# MAIN.net
KiCad netlist of a schematic drawn in Altium Designer
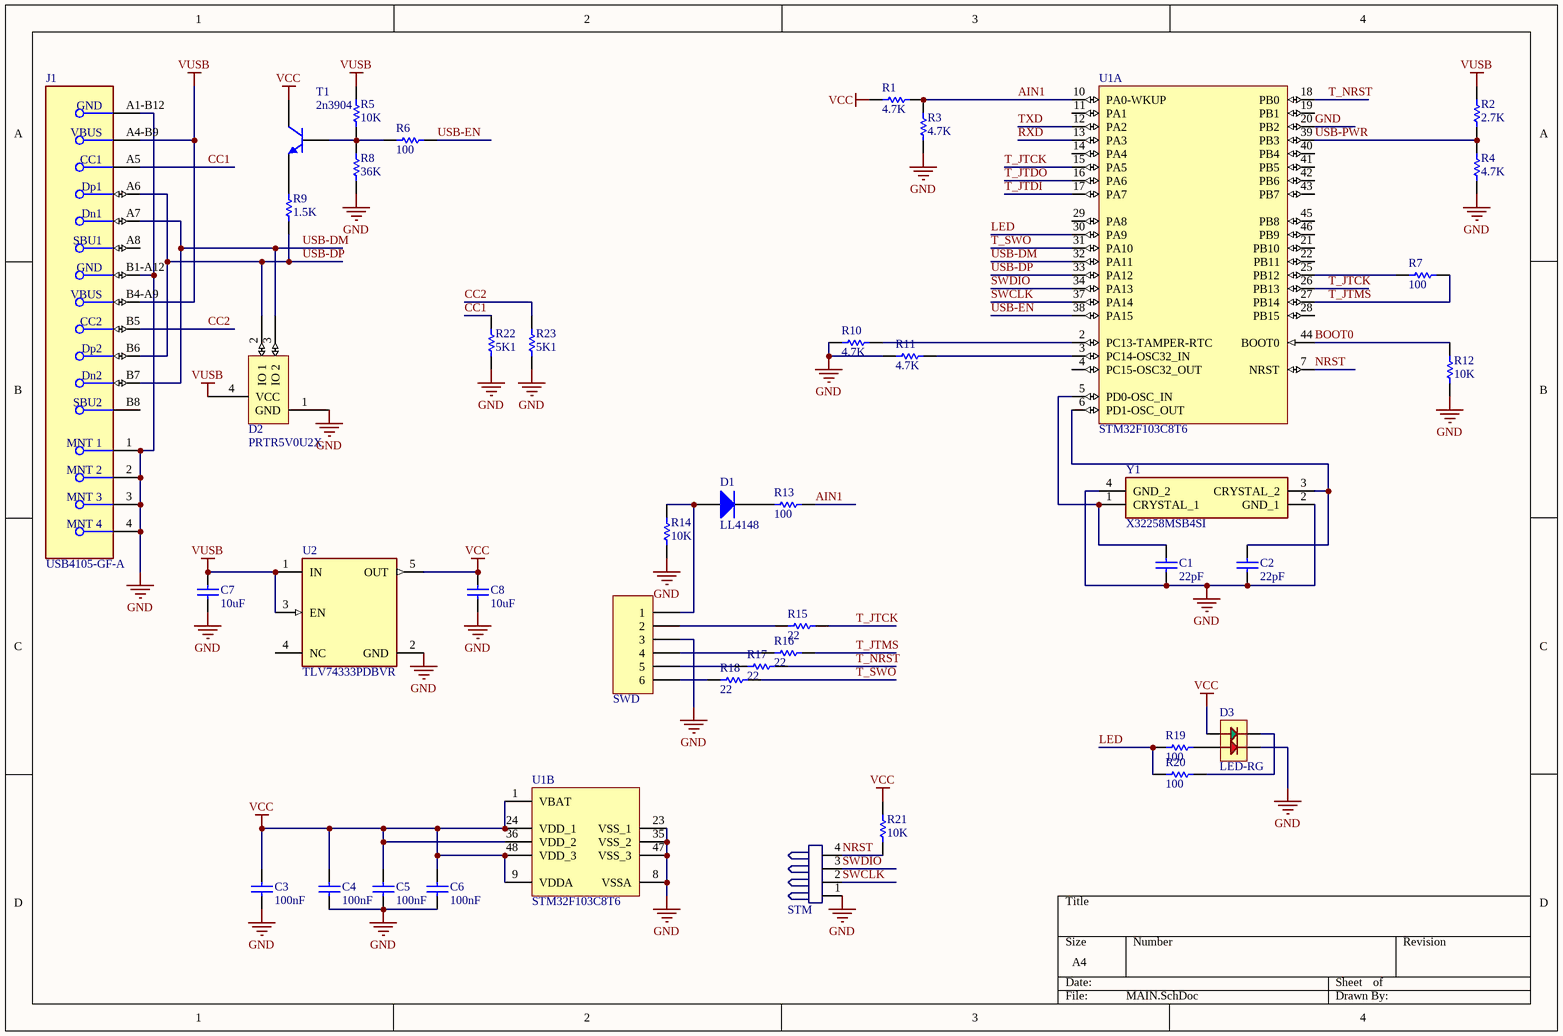
[diagram p0: MAIN.SchDoc]

(export (version "E")
  (design (tool "Eeschema 10.0.6"))
  (components
    (comp (ref "C1")
      (value "22pF")
      (footprint "C603")
      (description "Capacitor")
      (fields (field (name "DESIGNER") "Parsa Malekpour"))
      (libsource (lib "ParsaLibrary") (part "Cap"))
    )
    (comp (ref "C2")
      (value "22pF")
      (footprint "C603")
      (description "Capacitor")
      (fields (field (name "DESIGNER") "Parsa Malekpour"))
      (libsource (lib "ParsaLibrary") (part "Cap"))
    )
    (comp (ref "C3")
      (value "100nF")
      (footprint "C603")
      (description "Capacitor")
      (fields (field (name "DESIGNER") "Parsa Malekpour"))
      (libsource (lib "ParsaLibrary") (part "Cap"))
    )
    (comp (ref "C4")
      (value "100nF")
      (footprint "C603")
      (description "Capacitor")
      (fields (field (name "DESIGNER") "Parsa Malekpour"))
      (libsource (lib "ParsaLibrary") (part "Cap"))
    )
    (comp (ref "C5")
      (value "100nF")
      (footprint "C603")
      (description "Capacitor")
      (fields (field (name "DESIGNER") "Parsa Malekpour"))
      (libsource (lib "ParsaLibrary") (part "Cap"))
    )
    (comp (ref "C6")
      (value "100nF")
      (footprint "C603")
      (description "Capacitor")
      (fields (field (name "DESIGNER") "Parsa Malekpour"))
      (libsource (lib "ParsaLibrary") (part "Cap"))
    )
    (comp (ref "C7")
      (value "10uF")
      (footprint "C805")
      (description "Capacitor")
      (fields (field (name "DESIGNER") "Parsa Malekpour"))
      (libsource (lib "ParsaLibrary") (part "Cap"))
    )
    (comp (ref "C8")
      (value "10uF")
      (footprint "C805")
      (description "Capacitor")
      (fields (field (name "DESIGNER") "Parsa Malekpour"))
      (libsource (lib "ParsaLibrary") (part "Cap"))
    )
    (comp (ref "D1") (value "LL4148") (footprint "SOD-80") (libsource (lib "ParsaLibrary") (part "LL4148")))
    (comp (ref "D2")
      (value "PRTR5V0U2X")
      (footprint "SOT-143B")
      (description "Ultra low capacitance double rail-to-rail ESD protection diode")
      (libsource (lib "ParsaLibrary") (part "PRTR5V0U2X"))
    )
    (comp (ref "D3")
      (value "LED-RG")
      (footprint "LED-1210")
      (libsource (lib "ParsaLibrary") (part "LED-RG-4"))
    )
    (comp (ref "J1")
      (value "USB4105-GF-A")
      (footprint "FP-USB4105-GF-A-MFG")
      (description "CONN RCPT USB2.0 TYPEC 5A")
      (fields
        (field (name "MANUFACTURER") "GCT")
        (field (name "OCTOPART") "https://octopart.com/usb4105-gf-a-gct-106627878")
      )
      (libsource (lib "Altium Content Vault") (part "e7c17a616881a82b79941196b4bec10"))
    )
    (comp (ref "R1")
      (value "4.7K")
      (footprint "R0603")
      (description "Resistor")
      (fields (field (name "DESIGNER") "Parsa Malekpour"))
      (libsource (lib "ParsaLibrary") (part "Resistor"))
    )
    (comp (ref "R2")
      (value "2.7K")
      (footprint "R0603")
      (description "Resistor")
      (fields (field (name "DESIGNER") "Parsa Malekpour"))
      (libsource (lib "ParsaLibrary") (part "Resistor"))
    )
    (comp (ref "R3")
      (value "4.7K")
      (footprint "R0603")
      (description "Resistor")
      (fields (field (name "DESIGNER") "Parsa Malekpour"))
      (libsource (lib "ParsaLibrary") (part "Resistor"))
    )
    (comp (ref "R4")
      (value "4.7K")
      (footprint "R0603")
      (description "Resistor")
      (fields (field (name "DESIGNER") "Parsa Malekpour"))
      (libsource (lib "ParsaLibrary") (part "Resistor"))
    )
    (comp (ref "R5")
      (value "10K")
      (footprint "R0603")
      (description "Resistor")
      (fields (field (name "DESIGNER") "Parsa Malekpour"))
      (libsource (lib "ParsaLibrary") (part "Resistor"))
    )
    (comp (ref "R6")
      (value "100")
      (footprint "R0603")
      (description "Resistor")
      (fields (field (name "DESIGNER") "Parsa Malekpour"))
      (libsource (lib "ParsaLibrary") (part "Resistor"))
    )
    (comp (ref "R7")
      (value "100")
      (footprint "R0603")
      (description "Resistor")
      (fields (field (name "DESIGNER") "Parsa Malekpour"))
      (libsource (lib "ParsaLibrary") (part "Resistor"))
    )
    (comp (ref "R8")
      (value "36K")
      (footprint "R0603")
      (description "Resistor")
      (fields (field (name "DESIGNER") "Parsa Malekpour"))
      (libsource (lib "ParsaLibrary") (part "Resistor"))
    )
    (comp (ref "R9")
      (value "1.5K")
      (footprint "R0603")
      (description "Resistor")
      (fields (field (name "DESIGNER") "Parsa Malekpour"))
      (libsource (lib "ParsaLibrary") (part "Resistor"))
    )
    (comp (ref "R10")
      (value "4.7K")
      (footprint "R0603")
      (description "Resistor")
      (fields (field (name "DESIGNER") "Parsa Malekpour"))
      (libsource (lib "ParsaLibrary") (part "Resistor"))
    )
    (comp (ref "R11")
      (value "4.7K")
      (footprint "R0603")
      (description "Resistor")
      (fields (field (name "DESIGNER") "Parsa Malekpour"))
      (libsource (lib "ParsaLibrary") (part "Resistor"))
    )
    (comp (ref "R12")
      (value "10K")
      (footprint "R0603")
      (description "Resistor")
      (fields (field (name "DESIGNER") "Parsa Malekpour"))
      (libsource (lib "ParsaLibrary") (part "Resistor"))
    )
    (comp (ref "R13")
      (value "100")
      (footprint "R0603")
      (description "Resistor")
      (fields (field (name "DESIGNER") "Parsa Malekpour"))
      (libsource (lib "ParsaLibrary") (part "Resistor"))
    )
    (comp (ref "R14")
      (value "10K")
      (footprint "R0603")
      (description "Resistor")
      (fields (field (name "DESIGNER") "Parsa Malekpour"))
      (libsource (lib "ParsaLibrary") (part "Resistor"))
    )
    (comp (ref "R15")
      (value "22")
      (footprint "R0603")
      (description "Resistor")
      (fields (field (name "DESIGNER") "Parsa Malekpour"))
      (libsource (lib "ParsaLibrary") (part "Resistor"))
    )
    (comp (ref "R16")
      (value "22")
      (footprint "R0603")
      (description "Resistor")
      (fields (field (name "DESIGNER") "Parsa Malekpour"))
      (libsource (lib "ParsaLibrary") (part "Resistor"))
    )
    (comp (ref "R17")
      (value "22")
      (footprint "R0603")
      (description "Resistor")
      (fields (field (name "DESIGNER") "Parsa Malekpour"))
      (libsource (lib "ParsaLibrary") (part "Resistor"))
    )
    (comp (ref "R18")
      (value "22")
      (footprint "R0603")
      (description "Resistor")
      (fields (field (name "DESIGNER") "Parsa Malekpour"))
      (libsource (lib "ParsaLibrary") (part "Resistor"))
    )
    (comp (ref "R19")
      (value "100")
      (footprint "R0603")
      (description "Resistor")
      (fields (field (name "DESIGNER") "Parsa Malekpour"))
      (libsource (lib "ParsaLibrary") (part "Resistor"))
    )
    (comp (ref "R20")
      (value "100")
      (footprint "R0603")
      (description "Resistor")
      (fields (field (name "DESIGNER") "Parsa Malekpour"))
      (libsource (lib "ParsaLibrary") (part "Resistor"))
    )
    (comp (ref "R21")
      (value "10K")
      (footprint "R0603")
      (description "Resistor")
      (fields (field (name "DESIGNER") "Parsa Malekpour"))
      (libsource (lib "ParsaLibrary") (part "Resistor"))
    )
    (comp (ref "R22")
      (value "5K1")
      (footprint "R0603")
      (description "Resistor")
      (fields (field (name "DESIGNER") "Parsa Malekpour"))
      (libsource (lib "ParsaLibrary") (part "Resistor"))
    )
    (comp (ref "R23")
      (value "5K1")
      (footprint "R0603")
      (description "Resistor")
      (fields (field (name "DESIGNER") "Parsa Malekpour"))
      (libsource (lib "ParsaLibrary") (part "Resistor"))
    )
    (comp (ref "STM")
      (value "PHDR 4")
      (footprint "PH-4")
      (description "PinHeader")
      (libsource (lib "ParsaLibrary") (part "PHDR 4"))
    )
    (comp (ref "SWD") (value "CONN-6") (footprint "XH-6") (libsource (lib "ParsaLibrary") (part "CONN-6")))
    (comp (ref "T1") (value "2n3904") (footprint "SOT-23-3") (libsource (lib "ParsaLibrary") (part "2n3904")))
    (comp (ref "U1")
      (value "STM32F103C8T6")
      (footprint "LQFP-48")
      (libsource (lib "STMicroelectronics STM32 F1") (part "STM32F103C8T6"))
    )
    (comp (ref "U2")
      (value "TLV74333PDBVR")
      (footprint "FP-DBV0005A-MFG")
      (description "Linear Voltage Regulator IC  1 Output  300mA SOT-23-5")
      (fields (field (name "OCTOPART") "https://octopart.com/tlv74333pdbvr-texas+instruments-84791760"))
      (libsource (lib "Altium Content Vault") (part "3a8dd6e68b3b0d4ea301bae8a2f3989"))
    )
    (comp (ref "Y1")
      (value "X32258MSB4SI")
      (footprint "SamacSys:SMD3225_4P12288MHZ12PF10PPM4085")
      (description "Crystal or Oscillator")
      (fields (field (name "MANUFACTURER_PART_NUMBER") "SMD-3225_4P 12.288MHZ 12PF 10PPM -40~+85℃"))
      (libsource (lib "*") (part "SMD-3225_4P_12.288MHZ_12PF_10PPM_-40~+85"))
    )
  )
  (nets
    (net (code "1") (name "/AIN1") (class "Default")
      (node (ref "R1") (pin "1") (pinfunction "1_1") (pintype "passive"))
      (node (ref "R13") (pin "2") (pinfunction "2_2") (pintype "passive"))
      (node (ref "R3") (pin "2") (pinfunction "2_2") (pintype "passive"))
      (node (ref "U1") (pin "10") (pinfunction "PA0-WKUP_10") (pintype "bidirectional"))
    )
    (net (code "2") (name "/BOOT0") (class "Default")
      (node (ref "R12") (pin "2") (pinfunction "2_2") (pintype "passive"))
      (node (ref "U1") (pin "44") (pinfunction "BOOT0_44") (pintype "input"))
    )
    (net (code "3") (name "/CC1") (class "Default")
      (node (ref "J1") (pin "A5") (pinfunction "CC1_A5") (pintype "power_in"))
      (node (ref "R22") (pin "1") (pinfunction "1_1") (pintype "passive"))
    )
    (net (code "4") (name "/CC2") (class "Default")
      (node (ref "J1") (pin "B5") (pinfunction "CC2_B5") (pintype "bidirectional"))
      (node (ref "R23") (pin "1") (pinfunction "1_1") (pintype "passive"))
    )
    (net (code "5") (name "/LED") (class "Default")
      (node (ref "R19") (pin "2") (pinfunction "2_2") (pintype "passive"))
      (node (ref "R20") (pin "2") (pinfunction "2_2") (pintype "passive"))
      (node (ref "U1") (pin "30") (pinfunction "PA9_30") (pintype "bidirectional"))
    )
    (net (code "6") (name "/NRST") (class "Default")
      (node (ref "R21") (pin "1") (pinfunction "1_1") (pintype "passive"))
      (node (ref "STM") (pin "4") (pinfunction "4_4") (pintype "passive"))
      (node (ref "U1") (pin "7") (pinfunction "NRST_7") (pintype "bidirectional"))
    )
    (net (code "7") (name "/RXD") (class "Default")
      (node (ref "U1") (pin "13") (pinfunction "PA3_13") (pintype "bidirectional"))
    )
    (net (code "8") (name "/SWCLK") (class "Default")
      (node (ref "STM") (pin "2") (pinfunction "2_2") (pintype "passive"))
      (node (ref "U1") (pin "37") (pinfunction "PA14_37") (pintype "bidirectional"))
    )
    (net (code "9") (name "/SWDIO") (class "Default")
      (node (ref "STM") (pin "3") (pinfunction "3_3") (pintype "passive"))
      (node (ref "U1") (pin "34") (pinfunction "PA13_34") (pintype "bidirectional"))
    )
    (net (code "10") (name "/TXD") (class "Default")
      (node (ref "U1") (pin "12") (pinfunction "PA2_12") (pintype "bidirectional"))
    )
    (net (code "11") (name "/T_JTCK") (class "Default")
      (node (ref "R15") (pin "1") (pinfunction "1_1") (pintype "passive"))
      (node (ref "U1") (pin "15") (pinfunction "PA5_15") (pintype "bidirectional"))
      (node (ref "U1") (pin "26") (pinfunction "PB13_26") (pintype "bidirectional"))
    )
    (net (code "12") (name "/T_JTDI") (class "Default")
      (node (ref "U1") (pin "17") (pinfunction "PA7_17") (pintype "bidirectional"))
    )
    (net (code "13") (name "/T_JTDO") (class "Default")
      (node (ref "U1") (pin "16") (pinfunction "PA6_16") (pintype "bidirectional"))
    )
    (net (code "14") (name "/T_JTMS") (class "Default")
      (node (ref "R16") (pin "1") (pinfunction "1_1") (pintype "passive"))
      (node (ref "R7") (pin "1") (pinfunction "1_1") (pintype "passive"))
      (node (ref "U1") (pin "27") (pinfunction "PB14_27") (pintype "bidirectional"))
    )
    (net (code "15") (name "/T_NRST") (class "Default")
      (node (ref "R17") (pin "1") (pinfunction "1_1") (pintype "passive"))
      (node (ref "U1") (pin "18") (pinfunction "PB0_18") (pintype "bidirectional"))
    )
    (net (code "16") (name "/T_SWO") (class "Default")
      (node (ref "R18") (pin "1") (pinfunction "1_1") (pintype "passive"))
      (node (ref "U1") (pin "31") (pinfunction "PA10_31") (pintype "bidirectional"))
    )
    (net (code "17") (name "/USB-DM") (class "Default")
      (node (ref "D2") (pin "3") (pinfunction "IO_2_3") (pintype "bidirectional"))
      (node (ref "J1") (pin "A7") (pinfunction "Dn1_A7") (pintype "bidirectional"))
      (node (ref "J1") (pin "B7") (pinfunction "Dn2_B7") (pintype "bidirectional"))
      (node (ref "U1") (pin "32") (pinfunction "PA11_32") (pintype "bidirectional"))
    )
    (net (code "18") (name "/USB-DP") (class "Default")
      (node (ref "D2") (pin "2") (pinfunction "IO_1_2") (pintype "bidirectional"))
      (node (ref "J1") (pin "A6") (pinfunction "Dp1_A6") (pintype "bidirectional"))
      (node (ref "J1") (pin "B6") (pinfunction "Dp2_B6") (pintype "bidirectional"))
      (node (ref "R9") (pin "2") (pinfunction "2_2") (pintype "passive"))
      (node (ref "U1") (pin "33") (pinfunction "PA12_33") (pintype "bidirectional"))
    )
    (net (code "19") (name "/USB-EN") (class "Default")
      (node (ref "R6") (pin "2") (pinfunction "2_2") (pintype "passive"))
      (node (ref "U1") (pin "38") (pinfunction "PA15_38") (pintype "bidirectional"))
    )
    (net (code "20") (name "/USB-PWR") (class "Default")
      (node (ref "R2") (pin "2") (pinfunction "2_2") (pintype "passive"))
      (node (ref "R4") (pin "2") (pinfunction "2_2") (pintype "passive"))
      (node (ref "U1") (pin "39") (pinfunction "PB3_39") (pintype "bidirectional"))
    )
    (net (code "21") (name "GND") (class "Default")
      (node (ref "C1") (pin "1") (pinfunction "1_1") (pintype "passive"))
      (node (ref "C2") (pin "1") (pinfunction "1_1") (pintype "passive"))
      (node (ref "C3") (pin "1") (pinfunction "1_1") (pintype "passive"))
      (node (ref "C4") (pin "1") (pinfunction "1_1") (pintype "passive"))
      (node (ref "C5") (pin "1") (pinfunction "1_1") (pintype "passive"))
      (node (ref "C6") (pin "1") (pinfunction "1_1") (pintype "passive"))
      (node (ref "C7") (pin "1") (pinfunction "1_1") (pintype "passive"))
      (node (ref "C8") (pin "1") (pinfunction "1_1") (pintype "passive"))
      (node (ref "D2") (pin "1") (pinfunction "GND_1") (pintype "power_in"))
      (node (ref "D3") (pin "3") (pinfunction "RED-C_3") (pintype "passive"))
      (node (ref "J1") (pin "1") (pinfunction "MNT_1_1") (pintype "power_in"))
      (node (ref "J1") (pin "2") (pinfunction "MNT_2_2") (pintype "power_in"))
      (node (ref "J1") (pin "3") (pinfunction "MNT_3_3") (pintype "power_in"))
      (node (ref "J1") (pin "4") (pinfunction "MNT_4_4") (pintype "power_in"))
      (node (ref "J1") (pin "A1-B12") (pinfunction "GND_A1-B12") (pintype "power_in"))
      (node (ref "J1") (pin "B1-A12") (pinfunction "GND_B1-A12") (pintype "bidirectional"))
      (node (ref "R10") (pin "2") (pinfunction "2_2") (pintype "passive"))
      (node (ref "R11") (pin "2") (pinfunction "2_2") (pintype "passive"))
      (node (ref "R12") (pin "1") (pinfunction "1_1") (pintype "passive"))
      (node (ref "R14") (pin "2") (pinfunction "2_2") (pintype "passive"))
      (node (ref "R22") (pin "2") (pinfunction "2_2") (pintype "passive"))
      (node (ref "R23") (pin "2") (pinfunction "2_2") (pintype "passive"))
      (node (ref "R3") (pin "1") (pinfunction "1_1") (pintype "passive"))
      (node (ref "R4") (pin "1") (pinfunction "1_1") (pintype "passive"))
      (node (ref "R8") (pin "2") (pinfunction "2_2") (pintype "passive"))
      (node (ref "STM") (pin "1") (pinfunction "1_1") (pintype "passive"))
      (node (ref "SWD") (pin "3") (pinfunction "3_3") (pintype "passive"))
      (node (ref "U1") (pin "20") (pinfunction "PB2_20") (pintype "bidirectional"))
      (node (ref "U1") (pin "23") (pinfunction "VSS_1_23") (pintype "power_in"))
      (node (ref "U1") (pin "35") (pinfunction "VSS_2_35") (pintype "power_in"))
      (node (ref "U1") (pin "47") (pinfunction "VSS_3_47") (pintype "power_in"))
      (node (ref "U1") (pin "8") (pinfunction "VSSA_8") (pintype "power_in"))
      (node (ref "U2") (pin "2") (pinfunction "GND_2") (pintype "power_in"))
      (node (ref "Y1") (pin "2") (pinfunction "GND_1_2") (pintype "passive"))
      (node (ref "Y1") (pin "4") (pinfunction "GND_2_4") (pintype "passive"))
    )
    (net (code "22") (name "Net-(D1-A)") (class "Default")
      (node (ref "D1") (pin "1") (pinfunction "A_1") (pintype "passive"))
      (node (ref "R14") (pin "1") (pinfunction "1_1") (pintype "passive"))
      (node (ref "SWD") (pin "1") (pinfunction "1_1") (pintype "passive"))
    )
    (net (code "23") (name "Net-(D1-K)") (class "Default")
      (node (ref "D1") (pin "2") (pinfunction "K_2") (pintype "passive"))
      (node (ref "R13") (pin "1") (pinfunction "1_1") (pintype "passive"))
    )
    (net (code "24") (name "Net-(D3-GRN-C)") (class "Default")
      (node (ref "D3") (pin "4") (pinfunction "GRN-C_4") (pintype "passive"))
      (node (ref "R20") (pin "1") (pinfunction "1_1") (pintype "passive"))
    )
    (net (code "25") (name "Net-(D3-RED-A)") (class "Default")
      (node (ref "D3") (pin "2") (pinfunction "RED-A_2") (pintype "passive"))
      (node (ref "R19") (pin "1") (pinfunction "1_1") (pintype "passive"))
    )
    (net (code "26") (name "Net-(R15-Pad2)") (class "Default")
      (node (ref "R15") (pin "2") (pinfunction "2_2") (pintype "passive"))
      (node (ref "SWD") (pin "2") (pinfunction "2_2") (pintype "passive"))
    )
    (net (code "27") (name "Net-(R16-Pad2)") (class "Default")
      (node (ref "R16") (pin "2") (pinfunction "2_2") (pintype "passive"))
      (node (ref "SWD") (pin "4") (pinfunction "4_4") (pintype "passive"))
    )
    (net (code "28") (name "Net-(R17-Pad2)") (class "Default")
      (node (ref "R17") (pin "2") (pinfunction "2_2") (pintype "passive"))
      (node (ref "SWD") (pin "5") (pinfunction "5_5") (pintype "passive"))
    )
    (net (code "29") (name "Net-(R18-Pad2)") (class "Default")
      (node (ref "R18") (pin "2") (pinfunction "2_2") (pintype "passive"))
      (node (ref "SWD") (pin "6") (pinfunction "6_6") (pintype "passive"))
    )
    (net (code "30") (name "Net-(T1-B)") (class "Default")
      (node (ref "R5") (pin "2") (pinfunction "2_2") (pintype "passive"))
      (node (ref "R6") (pin "1") (pinfunction "1_1") (pintype "passive"))
      (node (ref "R8") (pin "1") (pinfunction "1_1") (pintype "passive"))
      (node (ref "T1") (pin "3") (pinfunction "B_3") (pintype "passive"))
    )
    (net (code "31") (name "Net-(T1-E)") (class "Default")
      (node (ref "R9") (pin "1") (pinfunction "1_1") (pintype "passive"))
      (node (ref "T1") (pin "2") (pinfunction "E_2") (pintype "passive"))
    )
    (net (code "32") (name "Net-(U1A-PB12)") (class "Default")
      (node (ref "R7") (pin "2") (pinfunction "2_2") (pintype "passive"))
      (node (ref "U1") (pin "25") (pinfunction "PB12_25") (pintype "bidirectional"))
    )
    (net (code "33") (name "Net-(U1A-PC13-TAMPER-RTC)") (class "Default")
      (node (ref "R10") (pin "1") (pinfunction "1_1") (pintype "passive"))
      (node (ref "U1") (pin "2") (pinfunction "PC13-TAMPER-RTC_2") (pintype "bidirectional"))
    )
    (net (code "34") (name "Net-(U1A-PC14-OSC32_IN)") (class "Default")
      (node (ref "R11") (pin "1") (pinfunction "1_1") (pintype "passive"))
      (node (ref "U1") (pin "3") (pinfunction "PC14-OSC32_IN_3") (pintype "bidirectional"))
    )
    (net (code "35") (name "Net-(U1A-PD0-OSC_IN)") (class "Default")
      (node (ref "C1") (pin "2") (pinfunction "2_2") (pintype "passive"))
      (node (ref "U1") (pin "5") (pinfunction "PD0-OSC_IN_5") (pintype "bidirectional"))
      (node (ref "Y1") (pin "1") (pinfunction "CRYSTAL_1_1") (pintype "passive"))
    )
    (net (code "36") (name "Net-(U1A-PD1-OSC_OUT)") (class "Default")
      (node (ref "C2") (pin "2") (pinfunction "2_2") (pintype "passive"))
      (node (ref "U1") (pin "6") (pinfunction "PD1-OSC_OUT_6") (pintype "bidirectional"))
      (node (ref "Y1") (pin "3") (pinfunction "CRYSTAL_2_3") (pintype "passive"))
    )
    (net (code "37") (name "VCC") (class "Default")
      (node (ref "C3") (pin "2") (pinfunction "2_2") (pintype "passive"))
      (node (ref "C4") (pin "2") (pinfunction "2_2") (pintype "passive"))
      (node (ref "C5") (pin "2") (pinfunction "2_2") (pintype "passive"))
      (node (ref "C6") (pin "2") (pinfunction "2_2") (pintype "passive"))
      (node (ref "C8") (pin "2") (pinfunction "2_2") (pintype "passive"))
      (node (ref "D3") (pin "1") (pinfunction "GRN-A_1") (pintype "passive"))
      (node (ref "R1") (pin "2") (pinfunction "2_2") (pintype "passive"))
      (node (ref "R21") (pin "2") (pinfunction "2_2") (pintype "passive"))
      (node (ref "T1") (pin "1") (pinfunction "C_1") (pintype "passive"))
      (node (ref "U1") (pin "1") (pinfunction "VBAT_1") (pintype "power_in"))
      (node (ref "U1") (pin "24") (pinfunction "VDD_1_24") (pintype "power_in"))
      (node (ref "U1") (pin "36") (pinfunction "VDD_2_36") (pintype "power_in"))
      (node (ref "U1") (pin "48") (pinfunction "VDD_3_48") (pintype "power_in"))
      (node (ref "U1") (pin "9") (pinfunction "VDDA_9") (pintype "power_in"))
      (node (ref "U2") (pin "5") (pinfunction "OUT_5") (pintype "output"))
    )
    (net (code "38") (name "VUSB") (class "Default")
      (node (ref "C7") (pin "2") (pinfunction "2_2") (pintype "passive"))
      (node (ref "D2") (pin "4") (pinfunction "VCC_4") (pintype "power_in"))
      (node (ref "J1") (pin "A4-B9") (pinfunction "VBUS_A4-B9") (pintype "power_in"))
      (node (ref "J1") (pin "B4-A9") (pinfunction "VBUS_B4-A9") (pintype "bidirectional"))
      (node (ref "R2") (pin "1") (pinfunction "1_1") (pintype "passive"))
      (node (ref "R5") (pin "1") (pinfunction "1_1") (pintype "passive"))
      (node (ref "U2") (pin "1") (pinfunction "IN_1") (pintype "power_in"))
      (node (ref "U2") (pin "3") (pinfunction "EN_3") (pintype "input"))
    )
    (net (code "39") (name "unconnected-(J1-SBU1-PadA8)") (class "Default")
      (node (ref "J1") (pin "A8") (pinfunction "SBU1_A8") (pintype "bidirectional"))
    )
    (net (code "40") (name "unconnected-(J1-SBU2-PadB8)") (class "Default")
      (node (ref "J1") (pin "B8") (pinfunction "SBU2_B8") (pintype "power_in"))
    )
    (net (code "41") (name "unconnected-(U1A-PA1-Pad11)") (class "Default")
      (node (ref "U1") (pin "11") (pinfunction "PA1_11") (pintype "bidirectional"))
    )
    (net (code "42") (name "unconnected-(U1A-PA4-Pad14)") (class "Default")
      (node (ref "U1") (pin "14") (pinfunction "PA4_14") (pintype "bidirectional"))
    )
    (net (code "43") (name "unconnected-(U1A-PA8-Pad29)") (class "Default")
      (node (ref "U1") (pin "29") (pinfunction "PA8_29") (pintype "bidirectional"))
    )
    (net (code "44") (name "unconnected-(U1A-PB1-Pad19)") (class "Default")
      (node (ref "U1") (pin "19") (pinfunction "PB1_19") (pintype "bidirectional"))
    )
    (net (code "45") (name "unconnected-(U1A-PB4-Pad40)") (class "Default")
      (node (ref "U1") (pin "40") (pinfunction "PB4_40") (pintype "bidirectional"))
    )
    (net (code "46") (name "unconnected-(U1A-PB5-Pad41)") (class "Default")
      (node (ref "U1") (pin "41") (pinfunction "PB5_41") (pintype "bidirectional"))
    )
    (net (code "47") (name "unconnected-(U1A-PB6-Pad42)") (class "Default")
      (node (ref "U1") (pin "42") (pinfunction "PB6_42") (pintype "bidirectional"))
    )
    (net (code "48") (name "unconnected-(U1A-PB7-Pad43)") (class "Default")
      (node (ref "U1") (pin "43") (pinfunction "PB7_43") (pintype "bidirectional"))
    )
    (net (code "49") (name "unconnected-(U1A-PB8-Pad45)") (class "Default")
      (node (ref "U1") (pin "45") (pinfunction "PB8_45") (pintype "bidirectional"))
    )
    (net (code "50") (name "unconnected-(U1A-PB9-Pad46)") (class "Default")
      (node (ref "U1") (pin "46") (pinfunction "PB9_46") (pintype "bidirectional"))
    )
    (net (code "51") (name "unconnected-(U1A-PB10-Pad21)") (class "Default")
      (node (ref "U1") (pin "21") (pinfunction "PB10_21") (pintype "bidirectional"))
    )
    (net (code "52") (name "unconnected-(U1A-PB11-Pad22)") (class "Default")
      (node (ref "U1") (pin "22") (pinfunction "PB11_22") (pintype "bidirectional"))
    )
    (net (code "53") (name "unconnected-(U1A-PB15-Pad28)") (class "Default")
      (node (ref "U1") (pin "28") (pinfunction "PB15_28") (pintype "bidirectional"))
    )
    (net (code "54") (name "unconnected-(U1A-PC15-OSC32_OUT-Pad4)") (class "Default")
      (node (ref "U1") (pin "4") (pinfunction "PC15-OSC32_OUT_4") (pintype "bidirectional"))
    )
    (net (code "55") (name "unconnected-(U2-NC-Pad4)") (class "Default")
      (node (ref "U2") (pin "4") (pinfunction "NC_4") (pintype "passive"))
    )
  )
)
